# Rocket_End_sensors.net
KiCad netlist of a schematic drawn in EAGLE
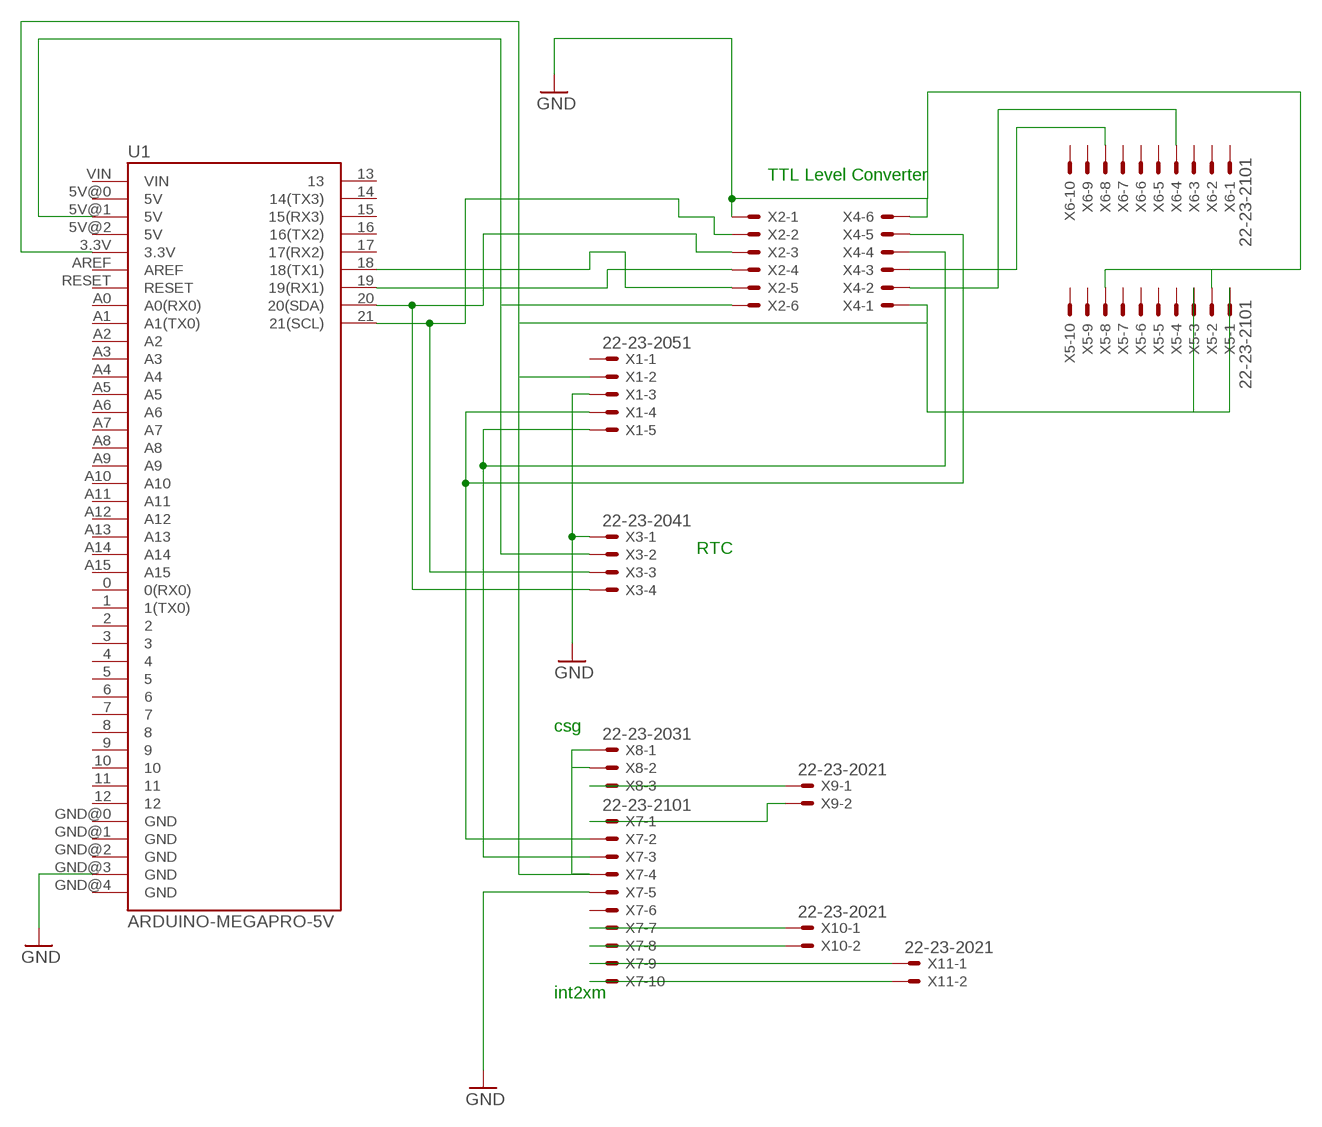
[diagram p0: schematic, sheet 1]

(export (version "E")
  (design (tool "Eeschema 10.0.6"))
  (components
    (comp (ref "U1")
      (value "ARDUINO-MEGAPRO-5V")
      (footprint "eagle-import:ARDUINO_MEGA-PRO-5V")
      (libsource (lib "eagle-import") (part "ARDUINO-MEGAPRO-5V"))
    )
    (comp (ref "X1")
      (value "22-23-2051")
      (footprint "eagle-import:22-23-2051")
      (fields (field (name "MF") "MOLEX"))
      (libsource (lib "eagle-import") (part "22-23-2051"))
    )
    (comp (ref "X2")
      (value "22-23-2061")
      (footprint "eagle-import:22-23-2061")
      (fields (field (name "MF") "MOLEX"))
      (libsource (lib "eagle-import") (part "22-23-2061"))
    )
    (comp (ref "X3")
      (value "22-23-2041")
      (footprint "eagle-import:22-23-2041")
      (fields (field (name "MF") "MOLEX"))
      (libsource (lib "eagle-import") (part "22-23-2041"))
    )
    (comp (ref "X4")
      (value "22-23-2061")
      (footprint "eagle-import:22-23-2061")
      (fields (field (name "MF") "MOLEX"))
      (libsource (lib "eagle-import") (part "22-23-2061"))
    )
    (comp (ref "X5")
      (value "22-23-2101")
      (footprint "eagle-import:22-23-2101")
      (fields (field (name "MF") "MOLEX"))
      (libsource (lib "eagle-import") (part "22-23-2101"))
    )
    (comp (ref "X6")
      (value "22-23-2101")
      (footprint "eagle-import:22-23-2101")
      (fields (field (name "MF") "MOLEX"))
      (libsource (lib "eagle-import") (part "22-23-2101"))
    )
    (comp (ref "X7")
      (value "22-23-2101")
      (footprint "eagle-import:22-23-2101")
      (fields (field (name "MF") "MOLEX"))
      (libsource (lib "eagle-import") (part "22-23-2101"))
    )
    (comp (ref "X8")
      (value "22-23-2031")
      (footprint "eagle-import:22-23-2031")
      (fields (field (name "MF") "MOLEX"))
      (libsource (lib "eagle-import") (part "22-23-2031"))
    )
    (comp (ref "X9")
      (value "22-23-2021")
      (footprint "eagle-import:22-23-2021")
      (fields (field (name "MF") "MOLEX"))
      (libsource (lib "eagle-import") (part "22-23-2021"))
    )
    (comp (ref "X10")
      (value "22-23-2021")
      (footprint "eagle-import:22-23-2021")
      (fields (field (name "MF") "MOLEX"))
      (libsource (lib "eagle-import") (part "22-23-2021"))
    )
    (comp (ref "X11")
      (value "22-23-2021")
      (footprint "eagle-import:22-23-2021")
      (fields (field (name "MF") "MOLEX"))
      (libsource (lib "eagle-import") (part "22-23-2021"))
    )
  )
  (nets
    (net (code "1") (name "GND") (class "Default")
      (node (ref "U1") (pin "GND@3") (pinfunction "GND_GND@3") (pintype "bidirectional"))
      (node (ref "X1") (pin "3") (pinfunction "S_3") (pintype "passive"))
      (node (ref "X2") (pin "1") (pinfunction "S_1") (pintype "passive"))
      (node (ref "X3") (pin "1") (pinfunction "S_1") (pintype "passive"))
      (node (ref "X4") (pin "6") (pinfunction "S_6") (pintype "passive"))
      (node (ref "X5") (pin "2") (pinfunction "S_2") (pintype "passive"))
      (node (ref "X5") (pin "8") (pinfunction "S_8") (pintype "passive"))
      (node (ref "X7") (pin "5") (pinfunction "S_5") (pintype "passive"))
    )
    (net (code "2") (name "Net-(U1-18(TX1))") (class "Default")
      (node (ref "U1") (pin "18") (pinfunction "18(TX1)_18") (pintype "bidirectional"))
      (node (ref "X2") (pin "5") (pinfunction "S_5") (pintype "passive"))
    )
    (net (code "3") (name "Net-(U1-19(RX1))") (class "Default")
      (node (ref "U1") (pin "19") (pinfunction "19(RX1)_19") (pintype "bidirectional"))
      (node (ref "X2") (pin "4") (pinfunction "S_4") (pintype "passive"))
    )
    (net (code "4") (name "Net-(U1-20(SDA))") (class "Default")
      (node (ref "U1") (pin "20") (pinfunction "20(SDA)_20") (pintype "bidirectional"))
      (node (ref "X2") (pin "3") (pinfunction "S_3") (pintype "passive"))
      (node (ref "X3") (pin "4") (pinfunction "S_4") (pintype "passive"))
    )
    (net (code "5") (name "Net-(U1-21(SCL))") (class "Default")
      (node (ref "U1") (pin "21") (pinfunction "21(SCL)_21") (pintype "bidirectional"))
      (node (ref "X2") (pin "2") (pinfunction "S_2") (pintype "passive"))
      (node (ref "X3") (pin "3") (pinfunction "S_3") (pintype "passive"))
    )
    (net (code "6") (name "Net-(X1B-S)") (class "Default")
      (node (ref "U1") (pin "3.3V") (pinfunction "3.3V_3.3V") (pintype "bidirectional"))
      (node (ref "X1") (pin "2") (pinfunction "S_2") (pintype "passive"))
      (node (ref "X4") (pin "1") (pinfunction "S_1") (pintype "passive"))
      (node (ref "X5") (pin "1") (pinfunction "S_1") (pintype "passive"))
      (node (ref "X5") (pin "3") (pinfunction "S_3") (pintype "passive"))
      (node (ref "X7") (pin "4") (pinfunction "S_4") (pintype "passive"))
      (node (ref "X8") (pin "1") (pinfunction "S_1") (pintype "passive"))
      (node (ref "X8") (pin "2") (pinfunction "S_2") (pintype "passive"))
    )
    (net (code "7") (name "Net-(X1D-S)") (class "Default")
      (node (ref "X1") (pin "4") (pinfunction "S_4") (pintype "passive"))
      (node (ref "X4") (pin "5") (pinfunction "S_5") (pintype "passive"))
      (node (ref "X7") (pin "2") (pinfunction "S_2") (pintype "passive"))
    )
    (net (code "8") (name "Net-(X1E-S)") (class "Default")
      (node (ref "X1") (pin "5") (pinfunction "S_5") (pintype "passive"))
      (node (ref "X4") (pin "4") (pinfunction "S_4") (pintype "passive"))
      (node (ref "X7") (pin "3") (pinfunction "S_3") (pintype "passive"))
    )
    (net (code "9") (name "Net-(X2F-S)") (class "Default")
      (node (ref "U1") (pin "5V@1") (pinfunction "5V_5V@1") (pintype "bidirectional"))
      (node (ref "X2") (pin "6") (pinfunction "S_6") (pintype "passive"))
      (node (ref "X3") (pin "2") (pinfunction "S_2") (pintype "passive"))
    )
    (net (code "10") (name "Net-(X4B-S)") (class "Default")
      (node (ref "X4") (pin "2") (pinfunction "S_2") (pintype "passive"))
      (node (ref "X6") (pin "4") (pinfunction "S_4") (pintype "passive"))
    )
    (net (code "11") (name "Net-(X4C-S)") (class "Default")
      (node (ref "X4") (pin "3") (pinfunction "S_3") (pintype "passive"))
      (node (ref "X6") (pin "8") (pinfunction "S_8") (pintype "passive"))
    )
    (net (code "12") (name "Net-(X7A-S)") (class "Default")
      (node (ref "X7") (pin "1") (pinfunction "S_1") (pintype "passive"))
      (node (ref "X9") (pin "2") (pinfunction "S_2") (pintype "passive"))
    )
    (net (code "13") (name "Net-(X8C-S)") (class "Default")
      (node (ref "X8") (pin "3") (pinfunction "S_3") (pintype "passive"))
      (node (ref "X9") (pin "1") (pinfunction "S_1") (pintype "passive"))
    )
    (net (code "14") (name "Net-(X10A-S)") (class "Default")
      (node (ref "X10") (pin "1") (pinfunction "S_1") (pintype "passive"))
      (node (ref "X7") (pin "7") (pinfunction "S_7") (pintype "passive"))
    )
    (net (code "15") (name "Net-(X10B-S)") (class "Default")
      (node (ref "X10") (pin "2") (pinfunction "S_2") (pintype "passive"))
      (node (ref "X7") (pin "8") (pinfunction "S_8") (pintype "passive"))
    )
    (net (code "16") (name "Net-(X11A-S)") (class "Default")
      (node (ref "X11") (pin "1") (pinfunction "S_1") (pintype "passive"))
      (node (ref "X7") (pin "9") (pinfunction "S_9") (pintype "passive"))
    )
    (net (code "17") (name "Net-(X11B-S)") (class "Default")
      (node (ref "X11") (pin "2") (pinfunction "S_2") (pintype "passive"))
      (node (ref "X7") (pin "10") (pinfunction "S_10") (pintype "passive"))
    )
    (net (code "18") (name "unconnected-(U1-0(RX0)-Pad0)") (class "Default")
      (node (ref "U1") (pin "0") (pinfunction "0(RX0)_0") (pintype "bidirectional"))
    )
    (net (code "19") (name "unconnected-(U1-1(TX0)-Pad1)") (class "Default")
      (node (ref "U1") (pin "1") (pinfunction "1(TX0)_1") (pintype "bidirectional"))
    )
    (net (code "20") (name "unconnected-(U1-5V-Pad5V@0)") (class "Default")
      (node (ref "U1") (pin "5V@0") (pinfunction "5V_5V@0") (pintype "bidirectional"))
    )
    (net (code "21") (name "unconnected-(U1-5V-Pad5V@2)") (class "Default")
      (node (ref "U1") (pin "5V@2") (pinfunction "5V_5V@2") (pintype "bidirectional"))
    )
    (net (code "22") (name "unconnected-(U1-14(TX3)-Pad14)") (class "Default")
      (node (ref "U1") (pin "14") (pinfunction "14(TX3)_14") (pintype "bidirectional"))
    )
    (net (code "23") (name "unconnected-(U1-15(RX3)-Pad15)") (class "Default")
      (node (ref "U1") (pin "15") (pinfunction "15(RX3)_15") (pintype "bidirectional"))
    )
    (net (code "24") (name "unconnected-(U1-16(TX2)-Pad16)") (class "Default")
      (node (ref "U1") (pin "16") (pinfunction "16(TX2)_16") (pintype "bidirectional"))
    )
    (net (code "25") (name "unconnected-(U1-17(RX2)-Pad17)") (class "Default")
      (node (ref "U1") (pin "17") (pinfunction "17(RX2)_17") (pintype "bidirectional"))
    )
    (net (code "26") (name "unconnected-(U1-A0(RX0)-PadA0)") (class "Default")
      (node (ref "U1") (pin "A0") (pinfunction "A0(RX0)_A0") (pintype "bidirectional"))
    )
    (net (code "27") (name "unconnected-(U1-A1(TX0)-PadA1)") (class "Default")
      (node (ref "U1") (pin "A1") (pinfunction "A1(TX0)_A1") (pintype "bidirectional"))
    )
    (net (code "28") (name "unconnected-(U1-GND-PadGND@0)") (class "Default")
      (node (ref "U1") (pin "GND@0") (pinfunction "GND_GND@0") (pintype "bidirectional"))
    )
    (net (code "29") (name "unconnected-(U1-GND-PadGND@1)") (class "Default")
      (node (ref "U1") (pin "GND@1") (pinfunction "GND_GND@1") (pintype "bidirectional"))
    )
    (net (code "30") (name "unconnected-(U1-GND-PadGND@2)") (class "Default")
      (node (ref "U1") (pin "GND@2") (pinfunction "GND_GND@2") (pintype "bidirectional"))
    )
    (net (code "31") (name "unconnected-(U1-GND-PadGND@4)") (class "Default")
      (node (ref "U1") (pin "GND@4") (pinfunction "GND_GND@4") (pintype "bidirectional"))
    )
    (net (code "32") (name "unconnected-(U1-Pad2)") (class "Default")
      (node (ref "U1") (pin "2") (pinfunction "2_2") (pintype "bidirectional"))
    )
    (net (code "33") (name "unconnected-(U1-Pad3)") (class "Default")
      (node (ref "U1") (pin "3") (pinfunction "3_3") (pintype "bidirectional"))
    )
    (net (code "34") (name "unconnected-(U1-Pad4)") (class "Default")
      (node (ref "U1") (pin "4") (pinfunction "4_4") (pintype "bidirectional"))
    )
    (net (code "35") (name "unconnected-(U1-Pad5)") (class "Default")
      (node (ref "U1") (pin "5") (pinfunction "5_5") (pintype "bidirectional"))
    )
    (net (code "36") (name "unconnected-(U1-Pad6)") (class "Default")
      (node (ref "U1") (pin "6") (pinfunction "6_6") (pintype "bidirectional"))
    )
    (net (code "37") (name "unconnected-(U1-Pad7)") (class "Default")
      (node (ref "U1") (pin "7") (pinfunction "7_7") (pintype "bidirectional"))
    )
    (net (code "38") (name "unconnected-(U1-Pad8)") (class "Default")
      (node (ref "U1") (pin "8") (pinfunction "8_8") (pintype "bidirectional"))
    )
    (net (code "39") (name "unconnected-(U1-Pad9)") (class "Default")
      (node (ref "U1") (pin "9") (pinfunction "9_9") (pintype "bidirectional"))
    )
    (net (code "40") (name "unconnected-(U1-Pad10)") (class "Default")
      (node (ref "U1") (pin "10") (pinfunction "10_10") (pintype "bidirectional"))
    )
    (net (code "41") (name "unconnected-(U1-Pad11)") (class "Default")
      (node (ref "U1") (pin "11") (pinfunction "11_11") (pintype "bidirectional"))
    )
    (net (code "42") (name "unconnected-(U1-Pad12)") (class "Default")
      (node (ref "U1") (pin "12") (pinfunction "12_12") (pintype "bidirectional"))
    )
    (net (code "43") (name "unconnected-(U1-Pad13)") (class "Default")
      (node (ref "U1") (pin "13") (pinfunction "13_13") (pintype "bidirectional"))
    )
    (net (code "44") (name "unconnected-(U1-PadA2)") (class "Default")
      (node (ref "U1") (pin "A2") (pinfunction "A2_A2") (pintype "bidirectional"))
    )
    (net (code "45") (name "unconnected-(U1-PadA3)") (class "Default")
      (node (ref "U1") (pin "A3") (pinfunction "A3_A3") (pintype "bidirectional"))
    )
    (net (code "46") (name "unconnected-(U1-PadA4)") (class "Default")
      (node (ref "U1") (pin "A4") (pinfunction "A4_A4") (pintype "bidirectional"))
    )
    (net (code "47") (name "unconnected-(U1-PadA5)") (class "Default")
      (node (ref "U1") (pin "A5") (pinfunction "A5_A5") (pintype "bidirectional"))
    )
    (net (code "48") (name "unconnected-(U1-PadA6)") (class "Default")
      (node (ref "U1") (pin "A6") (pinfunction "A6_A6") (pintype "bidirectional"))
    )
    (net (code "49") (name "unconnected-(U1-PadA7)") (class "Default")
      (node (ref "U1") (pin "A7") (pinfunction "A7_A7") (pintype "bidirectional"))
    )
    (net (code "50") (name "unconnected-(U1-PadA8)") (class "Default")
      (node (ref "U1") (pin "A8") (pinfunction "A8_A8") (pintype "bidirectional"))
    )
    (net (code "51") (name "unconnected-(U1-PadA9)") (class "Default")
      (node (ref "U1") (pin "A9") (pinfunction "A9_A9") (pintype "bidirectional"))
    )
    (net (code "52") (name "unconnected-(U1-PadA10)") (class "Default")
      (node (ref "U1") (pin "A10") (pinfunction "A10_A10") (pintype "bidirectional"))
    )
    (net (code "53") (name "unconnected-(U1-PadA11)") (class "Default")
      (node (ref "U1") (pin "A11") (pinfunction "A11_A11") (pintype "bidirectional"))
    )
    (net (code "54") (name "unconnected-(U1-PadA12)") (class "Default")
      (node (ref "U1") (pin "A12") (pinfunction "A12_A12") (pintype "bidirectional"))
    )
    (net (code "55") (name "unconnected-(U1-PadA13)") (class "Default")
      (node (ref "U1") (pin "A13") (pinfunction "A13_A13") (pintype "bidirectional"))
    )
    (net (code "56") (name "unconnected-(U1-PadA14)") (class "Default")
      (node (ref "U1") (pin "A14") (pinfunction "A14_A14") (pintype "bidirectional"))
    )
    (net (code "57") (name "unconnected-(U1-PadA15)") (class "Default")
      (node (ref "U1") (pin "A15") (pinfunction "A15_A15") (pintype "bidirectional"))
    )
    (net (code "58") (name "unconnected-(U1-PadAREF)") (class "Default")
      (node (ref "U1") (pin "AREF") (pinfunction "AREF_AREF") (pintype "bidirectional"))
    )
    (net (code "59") (name "unconnected-(U1-PadRESET)") (class "Default")
      (node (ref "U1") (pin "RESET") (pinfunction "RESET_RESET") (pintype "bidirectional"))
    )
    (net (code "60") (name "unconnected-(U1-PadVIN)") (class "Default")
      (node (ref "U1") (pin "VIN") (pinfunction "VIN_VIN") (pintype "bidirectional"))
    )
    (net (code "61") (name "unconnected-(X1A-S-Pad1)") (class "Default")
      (node (ref "X1") (pin "1") (pinfunction "S_1") (pintype "passive"))
    )
    (net (code "62") (name "unconnected-(X5B-S-Pad10)") (class "Default")
      (node (ref "X5") (pin "10") (pinfunction "S_10") (pintype "passive"))
    )
    (net (code "63") (name "unconnected-(X5E-S-Pad4)") (class "Default")
      (node (ref "X5") (pin "4") (pinfunction "S_4") (pintype "passive"))
    )
    (net (code "64") (name "unconnected-(X5F-S-Pad5)") (class "Default")
      (node (ref "X5") (pin "5") (pinfunction "S_5") (pintype "passive"))
    )
    (net (code "65") (name "unconnected-(X5G-S-Pad6)") (class "Default")
      (node (ref "X5") (pin "6") (pinfunction "S_6") (pintype "passive"))
    )
    (net (code "66") (name "unconnected-(X5H-S-Pad7)") (class "Default")
      (node (ref "X5") (pin "7") (pinfunction "S_7") (pintype "passive"))
    )
    (net (code "67") (name "unconnected-(X5J-S-Pad9)") (class "Default")
      (node (ref "X5") (pin "9") (pinfunction "S_9") (pintype "passive"))
    )
    (net (code "68") (name "unconnected-(X6A-S-Pad1)") (class "Default")
      (node (ref "X6") (pin "1") (pinfunction "S_1") (pintype "passive"))
    )
    (net (code "69") (name "unconnected-(X6B-S-Pad10)") (class "Default")
      (node (ref "X6") (pin "10") (pinfunction "S_10") (pintype "passive"))
    )
    (net (code "70") (name "unconnected-(X6C-S-Pad2)") (class "Default")
      (node (ref "X6") (pin "2") (pinfunction "S_2") (pintype "passive"))
    )
    (net (code "71") (name "unconnected-(X6D-S-Pad3)") (class "Default")
      (node (ref "X6") (pin "3") (pinfunction "S_3") (pintype "passive"))
    )
    (net (code "72") (name "unconnected-(X6F-S-Pad5)") (class "Default")
      (node (ref "X6") (pin "5") (pinfunction "S_5") (pintype "passive"))
    )
    (net (code "73") (name "unconnected-(X6G-S-Pad6)") (class "Default")
      (node (ref "X6") (pin "6") (pinfunction "S_6") (pintype "passive"))
    )
    (net (code "74") (name "unconnected-(X6H-S-Pad7)") (class "Default")
      (node (ref "X6") (pin "7") (pinfunction "S_7") (pintype "passive"))
    )
    (net (code "75") (name "unconnected-(X6J-S-Pad9)") (class "Default")
      (node (ref "X6") (pin "9") (pinfunction "S_9") (pintype "passive"))
    )
    (net (code "76") (name "unconnected-(X7G-S-Pad6)") (class "Default")
      (node (ref "X7") (pin "6") (pinfunction "S_6") (pintype "passive"))
    )
  )
)
